# BoardRev3.net
KiCad netlist of a schematic drawn in EAGLE
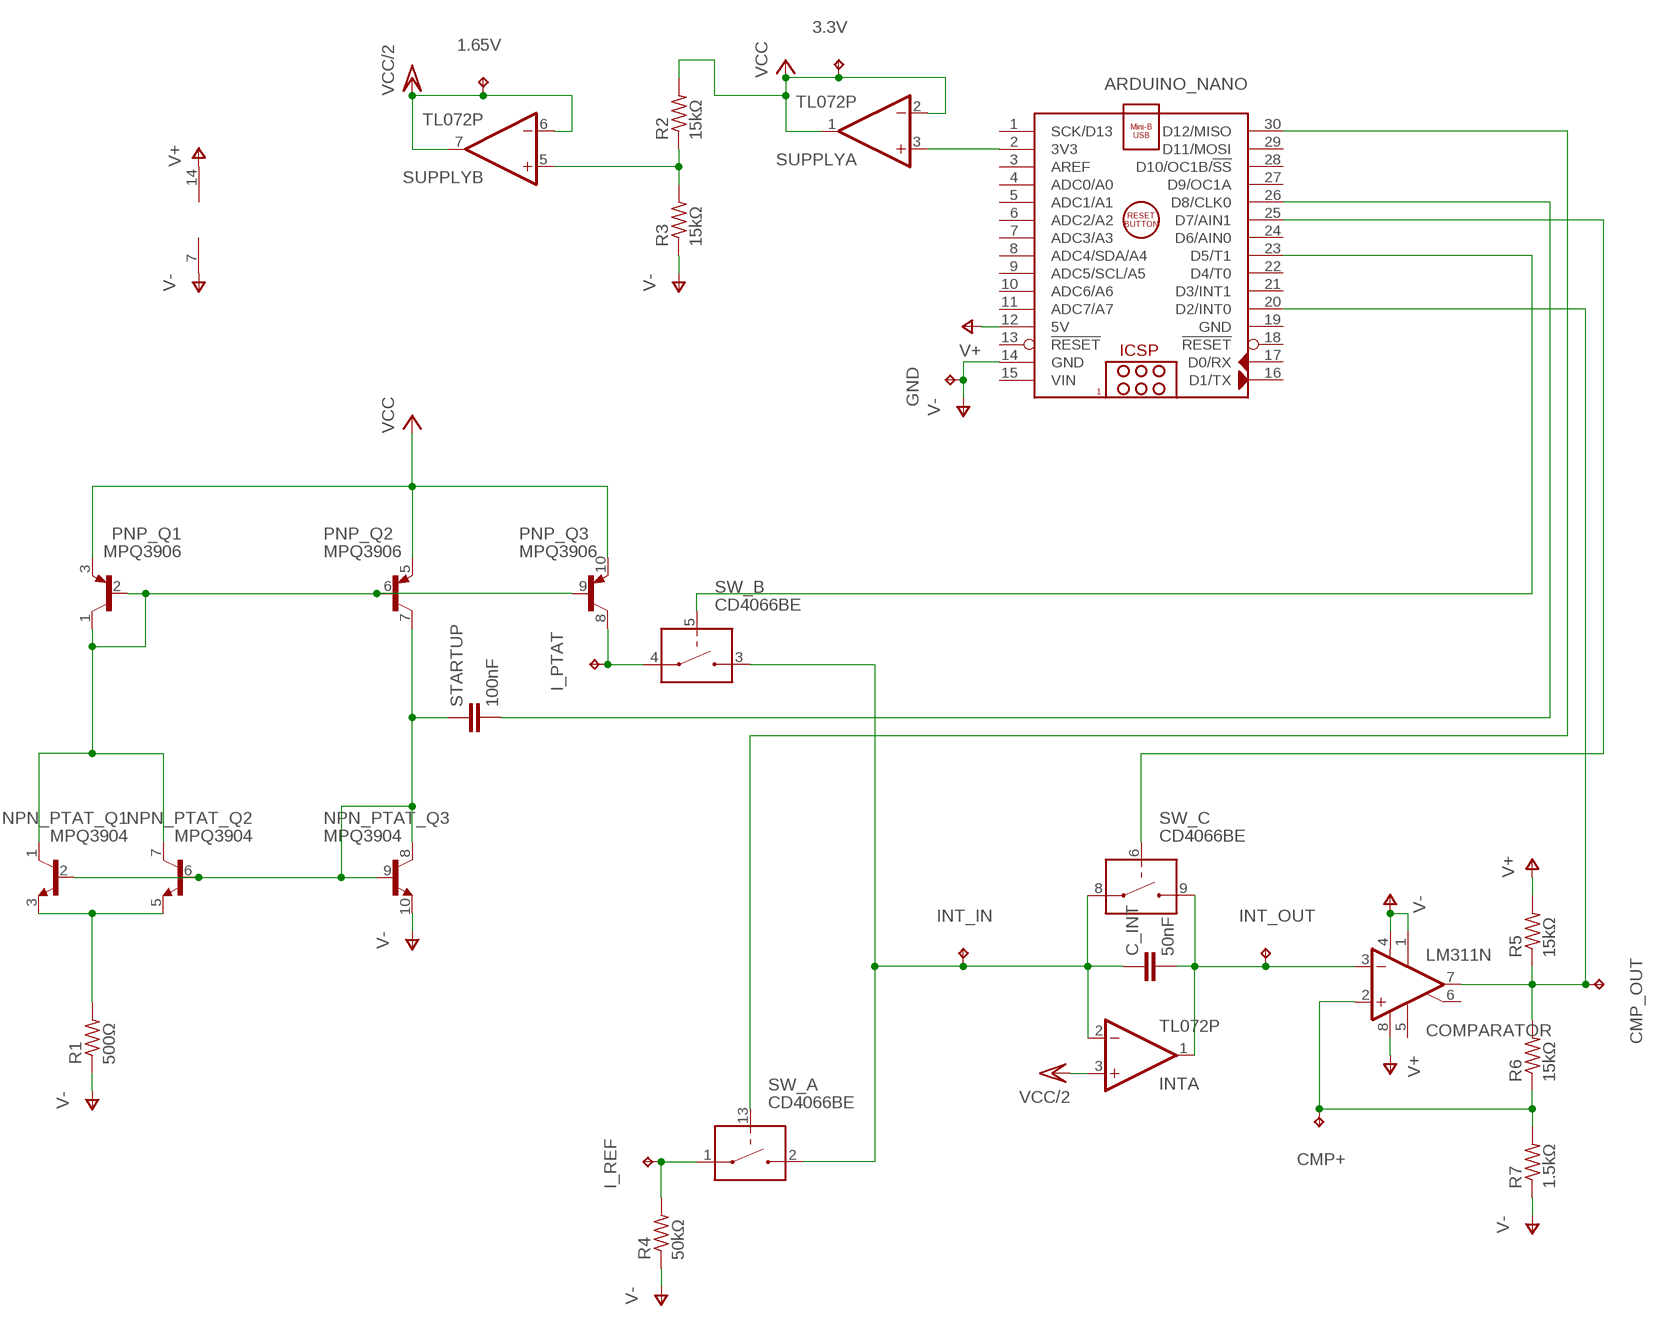
[diagram p0: schematic, sheet 1]

(export (version "E")
  (design (tool "Eeschema 10.0.6"))
  (components
    (comp (ref "1.65V")
      (value "TESTPOINT")
      (footprint "eagle-import:KEYSTONE_5000_MINIATURE")
      (libsource (lib "eagle-import") (part "TESTPOINT"))
    )
    (comp (ref "3.3V")
      (value "TESTPOINT")
      (footprint "eagle-import:KEYSTONE_5000_MINIATURE")
      (libsource (lib "eagle-import") (part "TESTPOINT"))
    )
    (comp (ref "ARDUINO_NANO")
      (value "ARDUINO_NANO")
      (footprint "eagle-import:ARDUINO_NANO")
      (libsource (lib "eagle-import") (part "ARDUINO_NANO"))
    )
    (comp (ref "CMP+")
      (value "TESTPOINT")
      (footprint "eagle-import:KEYSTONE_5000_MINIATURE")
      (libsource (lib "eagle-import") (part "TESTPOINT"))
    )
    (comp (ref "CMP_OUT")
      (value "TESTPOINT")
      (footprint "eagle-import:KEYSTONE_5000_MINIATURE")
      (libsource (lib "eagle-import") (part "TESTPOINT"))
    )
    (comp (ref "COMPARATOR")
      (value "LM311N")
      (footprint "eagle-import:DIL08")
      (libsource (lib "eagle-import") (part "LM311N"))
    )
    (comp (ref "C_INT")
      (value "50nF")
      (footprint "eagle-import:C025-025X050")
      (libsource (lib "eagle-import") (part "C-EU025-025X050"))
    )
    (comp (ref "GND")
      (value "TESTPOINT")
      (footprint "eagle-import:KEYSTONE_5000_MINIATURE")
      (libsource (lib "eagle-import") (part "TESTPOINT"))
    )
    (comp (ref "INT")
      (value "TL072P")
      (footprint "eagle-import:DIL08")
      (libsource (lib "eagle-import") (part "TL072P"))
    )
    (comp (ref "INT_IN")
      (value "TESTPOINT")
      (footprint "eagle-import:KEYSTONE_5000_MINIATURE")
      (libsource (lib "eagle-import") (part "TESTPOINT"))
    )
    (comp (ref "INT_OUT")
      (value "TESTPOINT")
      (footprint "eagle-import:KEYSTONE_5000_MINIATURE")
      (libsource (lib "eagle-import") (part "TESTPOINT"))
    )
    (comp (ref "I_PTAT")
      (value "TESTPOINT")
      (footprint "eagle-import:KEYSTONE_5000_MINIATURE")
      (libsource (lib "eagle-import") (part "TESTPOINT"))
    )
    (comp (ref "I_REF")
      (value "TESTPOINT")
      (footprint "eagle-import:KEYSTONE_5000_MINIATURE")
      (libsource (lib "eagle-import") (part "TESTPOINT"))
    )
    (comp (ref "NPN_PTAT")
      (value "MPQ3904")
      (footprint "eagle-import:DIL14")
      (libsource (lib "eagle-import") (part "MPQ3904"))
    )
    (comp (ref "PNP")
      (value "MPQ3906")
      (footprint "eagle-import:DIL14")
      (libsource (lib "eagle-import") (part "MPQ3906"))
    )
    (comp (ref "R1")
      (value "500Ω")
      (footprint "eagle-import:0207_10")
      (libsource (lib "eagle-import") (part "R-US_0207/10"))
    )
    (comp (ref "R2")
      (value "15kΩ")
      (footprint "eagle-import:0207_10")
      (libsource (lib "eagle-import") (part "R-US_0207/10"))
    )
    (comp (ref "R3")
      (value "15kΩ")
      (footprint "eagle-import:0207_10")
      (libsource (lib "eagle-import") (part "R-US_0207/10"))
    )
    (comp (ref "R4")
      (value "50kΩ")
      (footprint "eagle-import:0207_10")
      (libsource (lib "eagle-import") (part "R-US_0207/10"))
    )
    (comp (ref "R5")
      (value "15kΩ")
      (footprint "eagle-import:0207_10")
      (libsource (lib "eagle-import") (part "R-US_0207/10"))
    )
    (comp (ref "R6")
      (value "15kΩ")
      (footprint "eagle-import:0207_10")
      (libsource (lib "eagle-import") (part "R-US_0207/10"))
    )
    (comp (ref "R7")
      (value "1.5kΩ")
      (footprint "eagle-import:0207_10")
      (libsource (lib "eagle-import") (part "R-US_0207/10"))
    )
    (comp (ref "STARTUP")
      (value "100nF")
      (footprint "eagle-import:C050-030X075")
      (libsource (lib "eagle-import") (part "C-EU050-030X075"))
    )
    (comp (ref "SUPPLY")
      (value "TL072P")
      (footprint "eagle-import:DIL08")
      (libsource (lib "eagle-import") (part "TL072P"))
    )
    (comp (ref "SW")
      (value "CD4066BE")
      (footprint "eagle-import:DIL14")
      (libsource (lib "eagle-import") (part "CD4066BE"))
    )
  )
  (nets
    (net (code "1") (name "/GND") (class "Default")
      (node (ref "ARDUINO_NANO") (pin "19") (pinfunction "GND_19") (pintype "power_in"))
    )
    (net (code "2") (name "/VIN") (class "Default")
      (node (ref "ARDUINO_NANO") (pin "15") (pinfunction "VIN_15") (pintype "power_in"))
    )
    (net (code "3") (name "Net-(ARDUINO_NANO-3V3)") (class "Default")
      (node (ref "ARDUINO_NANO") (pin "2") (pinfunction "3V3_2") (pintype "output"))
      (node (ref "SUPPLY") (pin "3") (pinfunction "+IN_3") (pintype "input"))
    )
    (net (code "4") (name "Net-(ARDUINO_NANO-D2{slash}INT0)") (class "Default")
      (node (ref "ARDUINO_NANO") (pin "20") (pinfunction "D2/INT0_20") (pintype "bidirectional"))
      (node (ref "CMP_OUT") (pin "P$1") (pinfunction "P$1_P$1") (pintype "bidirectional"))
      (node (ref "COMPARATOR") (pin "7") (pinfunction "OUT_7") (pintype "output"))
      (node (ref "R5") (pin "1") (pinfunction "1_1") (pintype "passive"))
      (node (ref "R6") (pin "2") (pinfunction "2_2") (pintype "passive"))
    )
    (net (code "5") (name "Net-(ARDUINO_NANO-D5{slash}T1)") (class "Default")
      (node (ref "ARDUINO_NANO") (pin "23") (pinfunction "D5/T1_23") (pintype "bidirectional"))
      (node (ref "SW") (pin "5") (pinfunction "CONTROL_5") (pintype "bidirectional"))
    )
    (net (code "6") (name "Net-(ARDUINO_NANO-D7{slash}AIN1)") (class "Default")
      (node (ref "ARDUINO_NANO") (pin "25") (pinfunction "D7/AIN1_25") (pintype "bidirectional"))
      (node (ref "SW") (pin "6") (pinfunction "CONTROL_6") (pintype "bidirectional"))
    )
    (net (code "7") (name "Net-(ARDUINO_NANO-D8{slash}CLK0)") (class "Default")
      (node (ref "ARDUINO_NANO") (pin "26") (pinfunction "D8/CLK0_26") (pintype "bidirectional"))
      (node (ref "STARTUP") (pin "2") (pinfunction "2_2") (pintype "passive"))
    )
    (net (code "8") (name "Net-(ARDUINO_NANO-D12{slash}MISO)") (class "Default")
      (node (ref "ARDUINO_NANO") (pin "30") (pinfunction "D12/MISO_30") (pintype "bidirectional"))
      (node (ref "SW") (pin "13") (pinfunction "CONTROL_13") (pintype "bidirectional"))
    )
    (net (code "9") (name "Net-(COMPARATOR-+IN)") (class "Default")
      (node (ref "CMP+") (pin "P$1") (pinfunction "P$1_P$1") (pintype "bidirectional"))
      (node (ref "COMPARATOR") (pin "2") (pinfunction "+IN_2") (pintype "input"))
      (node (ref "R6") (pin "1") (pinfunction "1_1") (pintype "passive"))
      (node (ref "R7") (pin "2") (pinfunction "2_2") (pintype "passive"))
    )
    (net (code "10") (name "Net-(COMPARATOR--IN)") (class "Default")
      (node (ref "COMPARATOR") (pin "3") (pinfunction "-IN_3") (pintype "input"))
      (node (ref "C_INT") (pin "2") (pinfunction "2_2") (pintype "passive"))
      (node (ref "INT") (pin "1") (pinfunction "OUT_1") (pintype "output"))
      (node (ref "INT_OUT") (pin "P$1") (pinfunction "P$1_P$1") (pintype "bidirectional"))
      (node (ref "SW") (pin "9") (pinfunction "IN/OUT2_9") (pintype "bidirectional"))
    )
    (net (code "11") (name "Net-(INTA--IN)") (class "Default")
      (node (ref "C_INT") (pin "1") (pinfunction "1_1") (pintype "passive"))
      (node (ref "INT") (pin "2") (pinfunction "-IN_2") (pintype "input"))
      (node (ref "INT_IN") (pin "P$1") (pinfunction "P$1_P$1") (pintype "bidirectional"))
      (node (ref "SW") (pin "2") (pinfunction "IN/OUT2_2") (pintype "bidirectional"))
      (node (ref "SW") (pin "3") (pinfunction "IN/OUT2_3") (pintype "bidirectional"))
      (node (ref "SW") (pin "8") (pinfunction "IN/OUT1_8") (pintype "bidirectional"))
    )
    (net (code "12") (name "Net-(NPN_PTATA-B)") (class "Default")
      (node (ref "NPN_PTAT") (pin "2") (pinfunction "B_2") (pintype "passive"))
      (node (ref "NPN_PTAT") (pin "6") (pinfunction "B_6") (pintype "passive"))
      (node (ref "NPN_PTAT") (pin "8") (pinfunction "C_8") (pintype "passive"))
      (node (ref "NPN_PTAT") (pin "9") (pinfunction "B_9") (pintype "passive"))
      (node (ref "PNP") (pin "7") (pinfunction "C_7") (pintype "passive"))
      (node (ref "STARTUP") (pin "1") (pinfunction "1_1") (pintype "passive"))
    )
    (net (code "13") (name "Net-(NPN_PTATA-C)") (class "Default")
      (node (ref "NPN_PTAT") (pin "1") (pinfunction "C_1") (pintype "passive"))
      (node (ref "NPN_PTAT") (pin "7") (pinfunction "C_7") (pintype "passive"))
      (node (ref "PNP") (pin "1") (pinfunction "C_1") (pintype "passive"))
      (node (ref "PNP") (pin "2") (pinfunction "B_2") (pintype "passive"))
      (node (ref "PNP") (pin "6") (pinfunction "B_6") (pintype "passive"))
      (node (ref "PNP") (pin "9") (pinfunction "B_9") (pintype "passive"))
    )
    (net (code "14") (name "Net-(NPN_PTATA-E)") (class "Default")
      (node (ref "NPN_PTAT") (pin "3") (pinfunction "E_3") (pintype "passive"))
      (node (ref "NPN_PTAT") (pin "5") (pinfunction "E_5") (pintype "passive"))
      (node (ref "R1") (pin "2") (pinfunction "2_2") (pintype "passive"))
    )
    (net (code "15") (name "Net-(PNPC-C)") (class "Default")
      (node (ref "I_PTAT") (pin "P$1") (pinfunction "P$1_P$1") (pintype "bidirectional"))
      (node (ref "PNP") (pin "8") (pinfunction "C_8") (pintype "passive"))
      (node (ref "SW") (pin "4") (pinfunction "IN/OUT1_4") (pintype "bidirectional"))
    )
    (net (code "16") (name "Net-(SUPPLYB-+IN)") (class "Default")
      (node (ref "R2") (pin "1") (pinfunction "1_1") (pintype "passive"))
      (node (ref "R3") (pin "2") (pinfunction "2_2") (pintype "passive"))
      (node (ref "SUPPLY") (pin "5") (pinfunction "+IN_5") (pintype "input"))
    )
    (net (code "17") (name "Net-(SWB-IN{slash}OUT1)") (class "Default")
      (node (ref "I_REF") (pin "P$1") (pinfunction "P$1_P$1") (pintype "bidirectional"))
      (node (ref "R4") (pin "2") (pinfunction "2_2") (pintype "passive"))
      (node (ref "SW") (pin "1") (pinfunction "IN/OUT1_1") (pintype "bidirectional"))
    )
    (net (code "18") (name "V+") (class "Default")
      (node (ref "ARDUINO_NANO") (pin "12") (pinfunction "5V_12") (pintype "power_in"))
      (node (ref "COMPARATOR") (pin "8") (pinfunction "V+_8") (pintype "power_in"))
      (node (ref "R5") (pin "2") (pinfunction "2_2") (pintype "passive"))
      (node (ref "SW") (pin "14") (pinfunction "V+_14") (pintype "power_in"))
    )
    (net (code "19") (name "V-") (class "Default")
      (node (ref "ARDUINO_NANO") (pin "14") (pinfunction "GND_14") (pintype "power_in"))
      (node (ref "COMPARATOR") (pin "1") (pinfunction "GND_1") (pintype "passive"))
      (node (ref "COMPARATOR") (pin "4") (pinfunction "V-_4") (pintype "power_in"))
      (node (ref "GND") (pin "P$1") (pinfunction "P$1_P$1") (pintype "bidirectional"))
      (node (ref "NPN_PTAT") (pin "10") (pinfunction "E_10") (pintype "passive"))
      (node (ref "R1") (pin "1") (pinfunction "1_1") (pintype "passive"))
      (node (ref "R3") (pin "1") (pinfunction "1_1") (pintype "passive"))
      (node (ref "R4") (pin "1") (pinfunction "1_1") (pintype "passive"))
      (node (ref "R7") (pin "1") (pinfunction "1_1") (pintype "passive"))
      (node (ref "SW") (pin "7") (pinfunction "V-_7") (pintype "power_in"))
    )
    (net (code "20") (name "VCC") (class "Default")
      (node (ref "3.3V") (pin "P$1") (pinfunction "P$1_P$1") (pintype "bidirectional"))
      (node (ref "PNP") (pin "10") (pinfunction "E_10") (pintype "passive"))
      (node (ref "PNP") (pin "3") (pinfunction "E_3") (pintype "passive"))
      (node (ref "PNP") (pin "5") (pinfunction "E_5") (pintype "passive"))
      (node (ref "R2") (pin "2") (pinfunction "2_2") (pintype "passive"))
      (node (ref "SUPPLY") (pin "1") (pinfunction "OUT_1") (pintype "output"))
      (node (ref "SUPPLY") (pin "2") (pinfunction "-IN_2") (pintype "input"))
    )
    (net (code "21") (name "VCC{slash}2") (class "Default")
      (node (ref "1.65V") (pin "P$1") (pinfunction "P$1_P$1") (pintype "bidirectional"))
      (node (ref "INT") (pin "3") (pinfunction "+IN_3") (pintype "input"))
      (node (ref "SUPPLY") (pin "6") (pinfunction "-IN_6") (pintype "input"))
      (node (ref "SUPPLY") (pin "7") (pinfunction "OUT_7") (pintype "output"))
    )
    (net (code "22") (name "unconnected-(ARDUINO_NANO-ADC0{slash}A0-Pad4)") (class "Default")
      (node (ref "ARDUINO_NANO") (pin "4") (pinfunction "ADC0/A0_4") (pintype "bidirectional"))
    )
    (net (code "23") (name "unconnected-(ARDUINO_NANO-ADC1{slash}A1-Pad5)") (class "Default")
      (node (ref "ARDUINO_NANO") (pin "5") (pinfunction "ADC1/A1_5") (pintype "bidirectional"))
    )
    (net (code "24") (name "unconnected-(ARDUINO_NANO-ADC2{slash}A2-Pad6)") (class "Default")
      (node (ref "ARDUINO_NANO") (pin "6") (pinfunction "ADC2/A2_6") (pintype "bidirectional"))
    )
    (net (code "25") (name "unconnected-(ARDUINO_NANO-ADC3{slash}A3-Pad7)") (class "Default")
      (node (ref "ARDUINO_NANO") (pin "7") (pinfunction "ADC3/A3_7") (pintype "bidirectional"))
    )
    (net (code "26") (name "unconnected-(ARDUINO_NANO-ADC4{slash}SDA{slash}A4-Pad8)") (class "Default")
      (node (ref "ARDUINO_NANO") (pin "8") (pinfunction "ADC4/SDA/A4_8") (pintype "bidirectional"))
    )
    (net (code "27") (name "unconnected-(ARDUINO_NANO-ADC5{slash}SCL{slash}A5-Pad9)") (class "Default")
      (node (ref "ARDUINO_NANO") (pin "9") (pinfunction "ADC5/SCL/A5_9") (pintype "bidirectional"))
    )
    (net (code "28") (name "unconnected-(ARDUINO_NANO-ADC6{slash}A6-Pad10)") (class "Default")
      (node (ref "ARDUINO_NANO") (pin "10") (pinfunction "ADC6/A6_10") (pintype "bidirectional"))
    )
    (net (code "29") (name "unconnected-(ARDUINO_NANO-ADC7{slash}A7-Pad11)") (class "Default")
      (node (ref "ARDUINO_NANO") (pin "11") (pinfunction "ADC7/A7_11") (pintype "bidirectional"))
    )
    (net (code "30") (name "unconnected-(ARDUINO_NANO-AREF-Pad3)") (class "Default")
      (node (ref "ARDUINO_NANO") (pin "3") (pinfunction "AREF_3") (pintype "input"))
    )
    (net (code "31") (name "unconnected-(ARDUINO_NANO-D0{slash}RX-Pad17)") (class "Default")
      (node (ref "ARDUINO_NANO") (pin "17") (pinfunction "D0/RX_17") (pintype "bidirectional"))
    )
    (net (code "32") (name "unconnected-(ARDUINO_NANO-D1{slash}TX-Pad16)") (class "Default")
      (node (ref "ARDUINO_NANO") (pin "16") (pinfunction "D1/TX_16") (pintype "bidirectional"))
    )
    (net (code "33") (name "unconnected-(ARDUINO_NANO-D3{slash}INT1-Pad21)") (class "Default")
      (node (ref "ARDUINO_NANO") (pin "21") (pinfunction "D3/INT1_21") (pintype "bidirectional"))
    )
    (net (code "34") (name "unconnected-(ARDUINO_NANO-D4{slash}T0-Pad22)") (class "Default")
      (node (ref "ARDUINO_NANO") (pin "22") (pinfunction "D4/T0_22") (pintype "bidirectional"))
    )
    (net (code "35") (name "unconnected-(ARDUINO_NANO-D6{slash}AIN0-Pad24)") (class "Default")
      (node (ref "ARDUINO_NANO") (pin "24") (pinfunction "D6/AIN0_24") (pintype "bidirectional"))
    )
    (net (code "36") (name "unconnected-(ARDUINO_NANO-D9{slash}OC1A-Pad27)") (class "Default")
      (node (ref "ARDUINO_NANO") (pin "27") (pinfunction "D9/OC1A_27") (pintype "bidirectional"))
    )
    (net (code "37") (name "unconnected-(ARDUINO_NANO-D10{slash}OC1B{slash}~{SS}-Pad28)") (class "Default")
      (node (ref "ARDUINO_NANO") (pin "28") (pinfunction "D10/OC1B/~{SS}_28") (pintype "bidirectional"))
    )
    (net (code "38") (name "unconnected-(ARDUINO_NANO-D11{slash}MOSI-Pad29)") (class "Default")
      (node (ref "ARDUINO_NANO") (pin "29") (pinfunction "D11/MOSI_29") (pintype "bidirectional"))
    )
    (net (code "39") (name "unconnected-(ARDUINO_NANO-SCK{slash}D13-Pad1)") (class "Default")
      (node (ref "ARDUINO_NANO") (pin "1") (pinfunction "SCK/D13_1") (pintype "bidirectional"))
    )
    (net (code "40") (name "unconnected-(ARDUINO_NANO-~{RESET}-Pad13)") (class "Default")
      (node (ref "ARDUINO_NANO") (pin "13") (pinfunction "~{RESET}_13") (pintype "input"))
    )
    (net (code "41") (name "unconnected-(ARDUINO_NANO-~{RESET}-Pad18)") (class "Default")
      (node (ref "ARDUINO_NANO") (pin "18") (pinfunction "~{RESET}_18") (pintype "input"))
    )
    (net (code "42") (name "unconnected-(COMPARATOR-ON-Pad5)") (class "Default")
      (node (ref "COMPARATOR") (pin "5") (pinfunction "ON_5") (pintype "passive"))
    )
    (net (code "43") (name "unconnected-(COMPARATOR-ON{slash}STR-Pad6)") (class "Default")
      (node (ref "COMPARATOR") (pin "6") (pinfunction "ON/STR_6") (pintype "passive"))
    )
  )
)
